# untitled.net
KiCad netlist of a schematic drawn in EAGLE
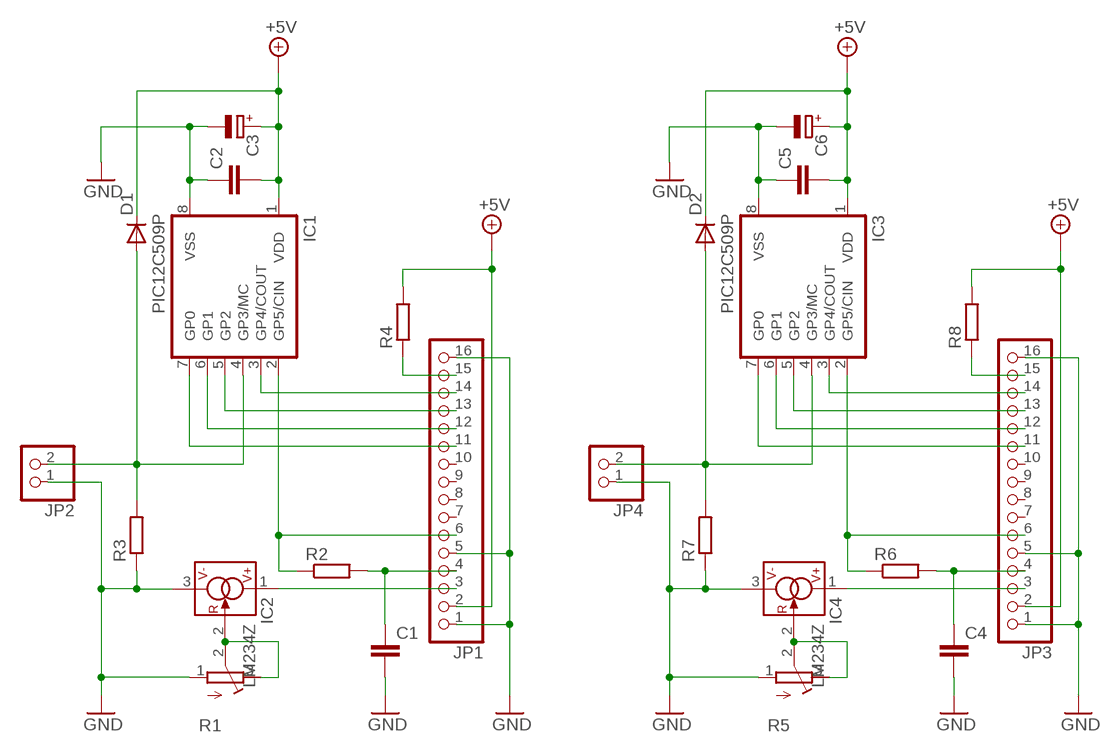
[diagram p0: schematic, sheet 1]

(export (version "E")
  (design (tool "Eeschema 10.0.6"))
  (components
    (comp (ref "C1")
      (value "C-EU025-025X050")
      (footprint "eagle-import:C025-025X050")
      (libsource (lib "eagle-import") (part "C-EU025-025X050"))
    )
    (comp (ref "C2")
      (value "C-EU025-025X050")
      (footprint "eagle-import:C025-025X050")
      (libsource (lib "eagle-import") (part "C-EU025-025X050"))
    )
    (comp (ref "C3")
      (value "CPOL-EUTT2D5L")
      (footprint "eagle-import:TT2D5L")
      (libsource (lib "eagle-import") (part "CPOL-EUTT2D5L"))
    )
    (comp (ref "C4")
      (value "C-EU025-025X050")
      (footprint "eagle-import:C025-025X050")
      (libsource (lib "eagle-import") (part "C-EU025-025X050"))
    )
    (comp (ref "C5")
      (value "C-EU025-025X050")
      (footprint "eagle-import:C025-025X050")
      (libsource (lib "eagle-import") (part "C-EU025-025X050"))
    )
    (comp (ref "C6")
      (value "CPOL-EUTT2D5L")
      (footprint "eagle-import:TT2D5L")
      (libsource (lib "eagle-import") (part "CPOL-EUTT2D5L"))
    )
    (comp (ref "D1")
      (value "DIODE-DO34-7")
      (footprint "eagle-import:DO34-7")
      (libsource (lib "eagle-import") (part "DIODE-DO34-7"))
    )
    (comp (ref "D2")
      (value "DIODE-DO34-7")
      (footprint "eagle-import:DO34-7")
      (libsource (lib "eagle-import") (part "DIODE-DO34-7"))
    )
    (comp (ref "IC1")
      (value "PIC12C509P")
      (footprint "eagle-import:DIL8")
      (fields (field (name "MF") "MICROCHIP") (field (name "MPN") "PIC12C509-04/P"))
      (libsource (lib "eagle-import") (part "PIC12C?P509"))
    )
    (comp (ref "IC2")
      (value "LM234Z")
      (footprint "eagle-import:TO92")
      (libsource (lib "eagle-import") (part "LM34Z2"))
    )
    (comp (ref "IC3")
      (value "PIC12C509P")
      (footprint "eagle-import:DIL8")
      (fields (field (name "MF") "MICROCHIP") (field (name "MPN") "PIC12C509-04/P"))
      (libsource (lib "eagle-import") (part "PIC12C?P509"))
    )
    (comp (ref "IC4")
      (value "LM234Z")
      (footprint "eagle-import:TO92")
      (libsource (lib "eagle-import") (part "LM34Z2"))
    )
    (comp (ref "JP1")
      (value "PINHD-1X16")
      (footprint "eagle-import:1X16")
      (libsource (lib "eagle-import") (part "PINHD-1X16"))
    )
    (comp (ref "JP2")
      (value "PINHD-1X2/90")
      (footprint "eagle-import:1X02_90")
      (libsource (lib "eagle-import") (part "PINHD-1X2/90"))
    )
    (comp (ref "JP3")
      (value "PINHD-1X16")
      (footprint "eagle-import:1X16")
      (libsource (lib "eagle-import") (part "PINHD-1X16"))
    )
    (comp (ref "JP4")
      (value "PINHD-1X2/90")
      (footprint "eagle-import:1X02_90")
      (libsource (lib "eagle-import") (part "PINHD-1X2/90"))
    )
    (comp (ref "R1")
      (value "R-TRIMM3296P")
      (footprint "eagle-import:RTRIM3296P")
      (libsource (lib "eagle-import") (part "R-TRIMM3296P"))
    )
    (comp (ref "R2")
      (value "R-EU_0204/7")
      (footprint "eagle-import:0204_7")
      (libsource (lib "eagle-import") (part "R-EU_0204/7"))
    )
    (comp (ref "R3")
      (value "R-EU_0204/7")
      (footprint "eagle-import:0204_7")
      (libsource (lib "eagle-import") (part "R-EU_0204/7"))
    )
    (comp (ref "R4")
      (value "R-EU_0204/7")
      (footprint "eagle-import:0204_7")
      (libsource (lib "eagle-import") (part "R-EU_0204/7"))
    )
    (comp (ref "R5")
      (value "R-TRIMM3296P")
      (footprint "eagle-import:RTRIM3296P")
      (libsource (lib "eagle-import") (part "R-TRIMM3296P"))
    )
    (comp (ref "R6")
      (value "R-EU_0204/7")
      (footprint "eagle-import:0204_7")
      (libsource (lib "eagle-import") (part "R-EU_0204/7"))
    )
    (comp (ref "R7")
      (value "R-EU_0204/7")
      (footprint "eagle-import:0204_7")
      (libsource (lib "eagle-import") (part "R-EU_0204/7"))
    )
    (comp (ref "R8")
      (value "R-EU_0207/12")
      (footprint "eagle-import:0207_12")
      (libsource (lib "eagle-import") (part "R-EU_0207/12"))
    )
  )
  (nets
    (net (code "1") (name "+5V") (class "Default")
      (node (ref "C2") (pin "2") (pinfunction "2_2") (pintype "passive"))
      (node (ref "C3") (pin "+") (pinfunction "+_+") (pintype "passive"))
      (node (ref "C5") (pin "2") (pinfunction "2_2") (pintype "passive"))
      (node (ref "C6") (pin "+") (pinfunction "+_+") (pintype "passive"))
      (node (ref "D1") (pin "C") (pinfunction "C_C") (pintype "passive"))
      (node (ref "D2") (pin "C") (pinfunction "C_C") (pintype "passive"))
      (node (ref "IC1") (pin "1") (pinfunction "VDD_1") (pintype "power_in"))
      (node (ref "IC3") (pin "1") (pinfunction "VDD_1") (pintype "power_in"))
      (node (ref "JP1") (pin "2") (pinfunction "2_2") (pintype "passive"))
      (node (ref "JP3") (pin "2") (pinfunction "2_2") (pintype "passive"))
      (node (ref "R4") (pin "2") (pinfunction "2_2") (pintype "passive"))
      (node (ref "R8") (pin "2") (pinfunction "2_2") (pintype "passive"))
    )
    (net (code "2") (name "GND") (class "Default")
      (node (ref "C1") (pin "2") (pinfunction "2_2") (pintype "passive"))
      (node (ref "C2") (pin "1") (pinfunction "1_1") (pintype "passive"))
      (node (ref "C3") (pin "-") (pinfunction "-_-") (pintype "passive"))
      (node (ref "C4") (pin "2") (pinfunction "2_2") (pintype "passive"))
      (node (ref "C5") (pin "1") (pinfunction "1_1") (pintype "passive"))
      (node (ref "C6") (pin "-") (pinfunction "-_-") (pintype "passive"))
      (node (ref "IC1") (pin "8") (pinfunction "VSS_8") (pintype "power_in"))
      (node (ref "IC2") (pin "3") (pinfunction "V-_3") (pintype "passive"))
      (node (ref "IC3") (pin "8") (pinfunction "VSS_8") (pintype "power_in"))
      (node (ref "IC4") (pin "3") (pinfunction "V-_3") (pintype "passive"))
      (node (ref "JP1") (pin "1") (pinfunction "1_1") (pintype "passive"))
      (node (ref "JP1") (pin "16") (pinfunction "16_16") (pintype "passive"))
      (node (ref "JP1") (pin "5") (pinfunction "5_5") (pintype "passive"))
      (node (ref "JP2") (pin "1") (pinfunction "1_1") (pintype "passive"))
      (node (ref "JP3") (pin "1") (pinfunction "1_1") (pintype "passive"))
      (node (ref "JP3") (pin "16") (pinfunction "16_16") (pintype "passive"))
      (node (ref "JP3") (pin "5") (pinfunction "5_5") (pintype "passive"))
      (node (ref "JP4") (pin "1") (pinfunction "1_1") (pintype "passive"))
      (node (ref "R1") (pin "1") (pinfunction "A_1") (pintype "passive"))
      (node (ref "R3") (pin "1") (pinfunction "1_1") (pintype "passive"))
      (node (ref "R5") (pin "1") (pinfunction "A_1") (pintype "passive"))
      (node (ref "R7") (pin "1") (pinfunction "1_1") (pintype "passive"))
    )
    (net (code "3") (name "Net-(C1-Pad1)") (class "Default")
      (node (ref "C1") (pin "1") (pinfunction "1_1") (pintype "passive"))
      (node (ref "JP1") (pin "4") (pinfunction "4_4") (pintype "passive"))
      (node (ref "R2") (pin "2") (pinfunction "2_2") (pintype "passive"))
    )
    (net (code "4") (name "Net-(C4-Pad1)") (class "Default")
      (node (ref "C4") (pin "1") (pinfunction "1_1") (pintype "passive"))
      (node (ref "JP3") (pin "4") (pinfunction "4_4") (pintype "passive"))
      (node (ref "R6") (pin "2") (pinfunction "2_2") (pintype "passive"))
    )
    (net (code "5") (name "Net-(IC1-GP0)") (class "Default")
      (node (ref "IC1") (pin "7") (pinfunction "GP0_7") (pintype "bidirectional"))
      (node (ref "JP1") (pin "11") (pinfunction "11_11") (pintype "passive"))
    )
    (net (code "6") (name "Net-(IC1-GP1)") (class "Default")
      (node (ref "IC1") (pin "6") (pinfunction "GP1_6") (pintype "bidirectional"))
      (node (ref "JP1") (pin "12") (pinfunction "12_12") (pintype "passive"))
    )
    (net (code "7") (name "Net-(IC1-GP2)") (class "Default")
      (node (ref "IC1") (pin "5") (pinfunction "GP2_5") (pintype "bidirectional"))
      (node (ref "JP1") (pin "13") (pinfunction "13_13") (pintype "passive"))
    )
    (net (code "8") (name "Net-(IC1-GP3{slash}MC)") (class "Default")
      (node (ref "D1") (pin "A") (pinfunction "A_A") (pintype "passive"))
      (node (ref "IC1") (pin "4") (pinfunction "GP3/MC_4") (pintype "input"))
      (node (ref "JP2") (pin "2") (pinfunction "2_2") (pintype "passive"))
      (node (ref "R3") (pin "2") (pinfunction "2_2") (pintype "passive"))
    )
    (net (code "9") (name "Net-(IC1-GP4{slash}COUT)") (class "Default")
      (node (ref "IC1") (pin "3") (pinfunction "GP4/COUT_3") (pintype "bidirectional"))
      (node (ref "JP1") (pin "14") (pinfunction "14_14") (pintype "passive"))
    )
    (net (code "10") (name "Net-(IC1-GP5{slash}CIN)") (class "Default")
      (node (ref "IC1") (pin "2") (pinfunction "GP5/CIN_2") (pintype "bidirectional"))
      (node (ref "JP1") (pin "6") (pinfunction "6_6") (pintype "passive"))
      (node (ref "R2") (pin "1") (pinfunction "1_1") (pintype "passive"))
    )
    (net (code "11") (name "Net-(IC2-R)") (class "Default")
      (node (ref "IC2") (pin "2") (pinfunction "R_2") (pintype "passive"))
      (node (ref "R1") (pin "2") (pinfunction "S_2") (pintype "passive"))
      (node (ref "R1") (pin "3") (pinfunction "E_3") (pintype "passive"))
    )
    (net (code "12") (name "Net-(IC2-V+)") (class "Default")
      (node (ref "IC2") (pin "1") (pinfunction "V+_1") (pintype "passive"))
      (node (ref "JP1") (pin "3") (pinfunction "3_3") (pintype "passive"))
    )
    (net (code "13") (name "Net-(IC3-GP0)") (class "Default")
      (node (ref "IC3") (pin "7") (pinfunction "GP0_7") (pintype "bidirectional"))
      (node (ref "JP3") (pin "11") (pinfunction "11_11") (pintype "passive"))
    )
    (net (code "14") (name "Net-(IC3-GP1)") (class "Default")
      (node (ref "IC3") (pin "6") (pinfunction "GP1_6") (pintype "bidirectional"))
      (node (ref "JP3") (pin "12") (pinfunction "12_12") (pintype "passive"))
    )
    (net (code "15") (name "Net-(IC3-GP2)") (class "Default")
      (node (ref "IC3") (pin "5") (pinfunction "GP2_5") (pintype "bidirectional"))
      (node (ref "JP3") (pin "13") (pinfunction "13_13") (pintype "passive"))
    )
    (net (code "16") (name "Net-(IC3-GP3{slash}MC)") (class "Default")
      (node (ref "D2") (pin "A") (pinfunction "A_A") (pintype "passive"))
      (node (ref "IC3") (pin "4") (pinfunction "GP3/MC_4") (pintype "input"))
      (node (ref "JP4") (pin "2") (pinfunction "2_2") (pintype "passive"))
      (node (ref "R7") (pin "2") (pinfunction "2_2") (pintype "passive"))
    )
    (net (code "17") (name "Net-(IC3-GP4{slash}COUT)") (class "Default")
      (node (ref "IC3") (pin "3") (pinfunction "GP4/COUT_3") (pintype "bidirectional"))
      (node (ref "JP3") (pin "14") (pinfunction "14_14") (pintype "passive"))
    )
    (net (code "18") (name "Net-(IC3-GP5{slash}CIN)") (class "Default")
      (node (ref "IC3") (pin "2") (pinfunction "GP5/CIN_2") (pintype "bidirectional"))
      (node (ref "JP3") (pin "6") (pinfunction "6_6") (pintype "passive"))
      (node (ref "R6") (pin "1") (pinfunction "1_1") (pintype "passive"))
    )
    (net (code "19") (name "Net-(IC4-R)") (class "Default")
      (node (ref "IC4") (pin "2") (pinfunction "R_2") (pintype "passive"))
      (node (ref "R5") (pin "2") (pinfunction "S_2") (pintype "passive"))
      (node (ref "R5") (pin "3") (pinfunction "E_3") (pintype "passive"))
    )
    (net (code "20") (name "Net-(IC4-V+)") (class "Default")
      (node (ref "IC4") (pin "1") (pinfunction "V+_1") (pintype "passive"))
      (node (ref "JP3") (pin "3") (pinfunction "3_3") (pintype "passive"))
    )
    (net (code "21") (name "Net-(JP1-Pad15)") (class "Default")
      (node (ref "JP1") (pin "15") (pinfunction "15_15") (pintype "passive"))
      (node (ref "R4") (pin "1") (pinfunction "1_1") (pintype "passive"))
    )
    (net (code "22") (name "Net-(JP3-Pad15)") (class "Default")
      (node (ref "JP3") (pin "15") (pinfunction "15_15") (pintype "passive"))
      (node (ref "R8") (pin "1") (pinfunction "1_1") (pintype "passive"))
    )
    (net (code "23") (name "unconnected-(JP1-Pad7)") (class "Default")
      (node (ref "JP1") (pin "7") (pinfunction "7_7") (pintype "passive"))
    )
    (net (code "24") (name "unconnected-(JP1-Pad8)") (class "Default")
      (node (ref "JP1") (pin "8") (pinfunction "8_8") (pintype "passive"))
    )
    (net (code "25") (name "unconnected-(JP1-Pad9)") (class "Default")
      (node (ref "JP1") (pin "9") (pinfunction "9_9") (pintype "passive"))
    )
    (net (code "26") (name "unconnected-(JP1-Pad10)") (class "Default")
      (node (ref "JP1") (pin "10") (pinfunction "10_10") (pintype "passive"))
    )
    (net (code "27") (name "unconnected-(JP3-Pad7)") (class "Default")
      (node (ref "JP3") (pin "7") (pinfunction "7_7") (pintype "passive"))
    )
    (net (code "28") (name "unconnected-(JP3-Pad8)") (class "Default")
      (node (ref "JP3") (pin "8") (pinfunction "8_8") (pintype "passive"))
    )
    (net (code "29") (name "unconnected-(JP3-Pad9)") (class "Default")
      (node (ref "JP3") (pin "9") (pinfunction "9_9") (pintype "passive"))
    )
    (net (code "30") (name "unconnected-(JP3-Pad10)") (class "Default")
      (node (ref "JP3") (pin "10") (pinfunction "10_10") (pintype "passive"))
    )
  )
)
